# MICROCONTROLLER.net
KiCad netlist of a schematic drawn in Altium Designer
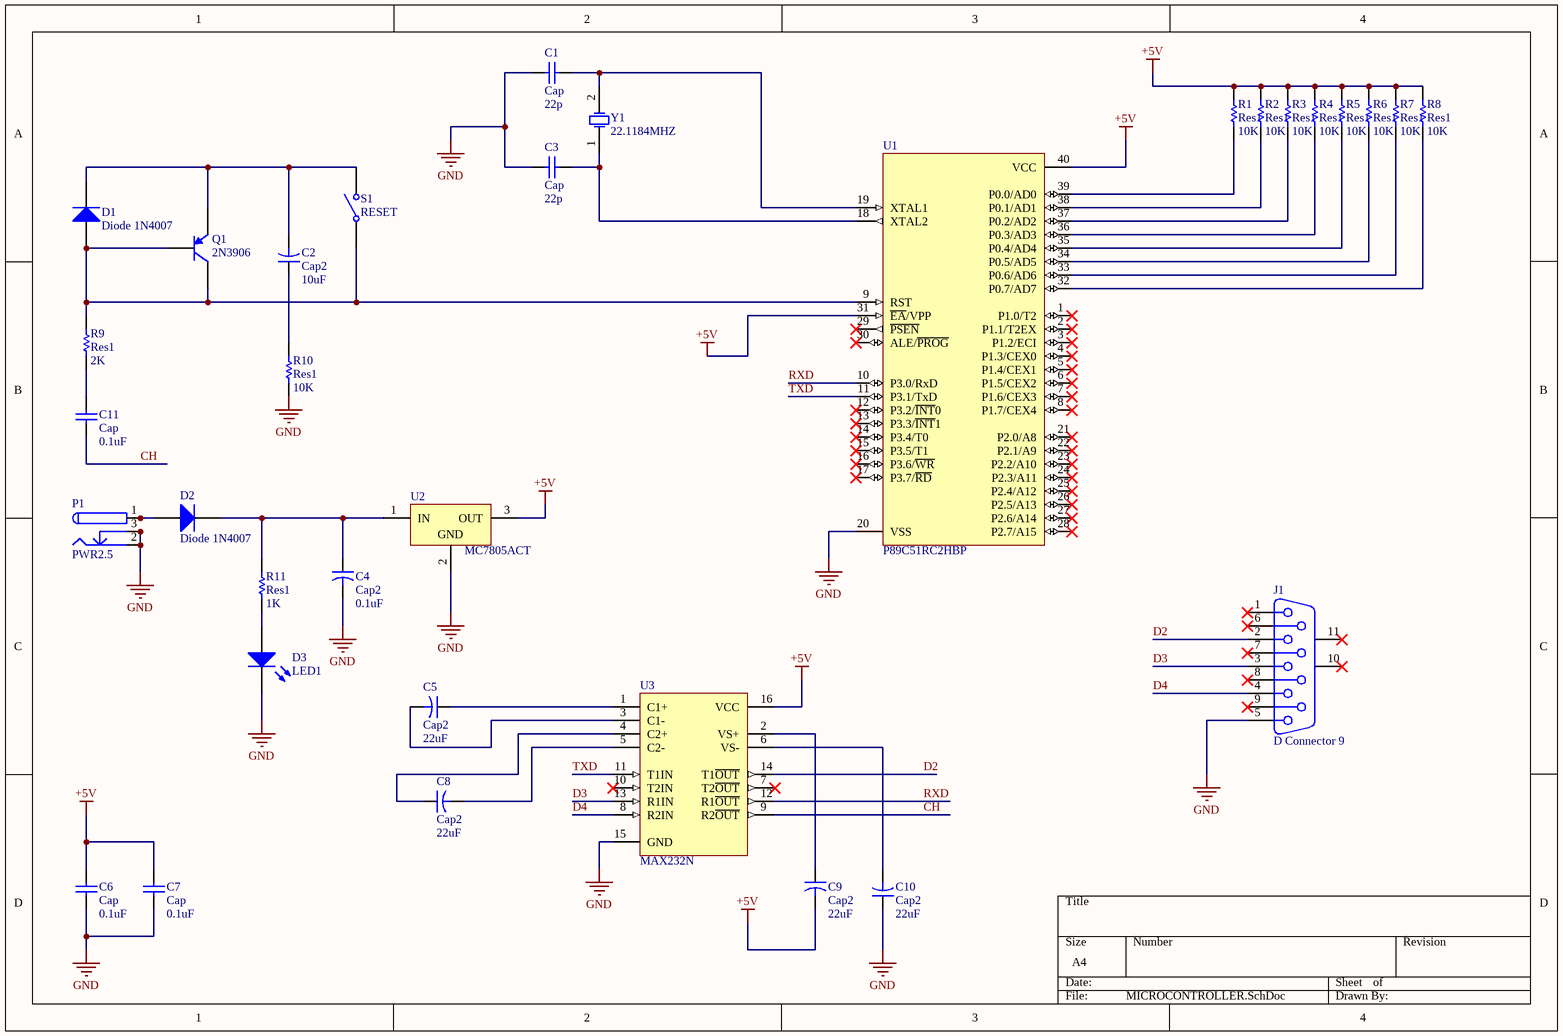
[diagram p0: MICROCONTROLLER.SchDoc]

(export (version "E")
  (design (tool "Eeschema 10.0.6"))
  (components
    (comp (ref "C1")
      (value "Cap")
      (footprint "CAPR2.54-5.1x3.2")
      (description "Capacitor")
      (fields (field (name "ALTIUM_VALUE") "22p") (field (name "PUBLISHER") "Altium Limited"))
      (libsource (lib "Miscellaneous Devices") (part "Cap"))
    )
    (comp (ref "C2")
      (value "Cap2")
      (footprint "CAPR5-4X5")
      (description "Capacitor")
      (fields (field (name "ALTIUM_VALUE") "10uF") (field (name "PUBLISHER") "Altium Limited"))
      (libsource (lib "Miscellaneous Devices") (part "Cap2"))
    )
    (comp (ref "C3")
      (value "Cap")
      (footprint "CAPR2.54-5.1x3.2")
      (description "Capacitor")
      (fields (field (name "ALTIUM_VALUE") "22p") (field (name "PUBLISHER") "Altium Limited"))
      (libsource (lib "Miscellaneous Devices") (part "Cap"))
    )
    (comp (ref "C4")
      (value "Cap2")
      (footprint "CAPR5-4X5")
      (description "Capacitor")
      (fields (field (name "ALTIUM_VALUE") "0.1uF") (field (name "PUBLISHER") "Altium Limited"))
      (libsource (lib "Miscellaneous Devices") (part "Cap2"))
    )
    (comp (ref "C5")
      (value "Cap2")
      (footprint "CAPR5-4X5")
      (description "Capacitor")
      (fields (field (name "ALTIUM_VALUE") "22uF") (field (name "PUBLISHER") "Altium Limited"))
      (libsource (lib "Miscellaneous Devices") (part "Cap2"))
    )
    (comp (ref "C6")
      (value "Cap")
      (footprint "CAPR2.54-5.1x3.2")
      (description "Capacitor")
      (fields (field (name "ALTIUM_VALUE") "0.1uF") (field (name "PUBLISHER") "Altium Limited"))
      (libsource (lib "Miscellaneous Devices") (part "Cap"))
    )
    (comp (ref "C7")
      (value "Cap")
      (footprint "CAPR2.54-5.1x3.2")
      (description "Capacitor")
      (fields (field (name "ALTIUM_VALUE") "0.1uF") (field (name "PUBLISHER") "Altium Limited"))
      (libsource (lib "Miscellaneous Devices") (part "Cap"))
    )
    (comp (ref "C8")
      (value "Cap2")
      (footprint "CAPR5-4X5")
      (description "Capacitor")
      (fields (field (name "ALTIUM_VALUE") "22uF") (field (name "PUBLISHER") "Altium Limited"))
      (libsource (lib "Miscellaneous Devices") (part "Cap2"))
    )
    (comp (ref "C9")
      (value "Cap2")
      (footprint "CAPR5-4X5")
      (description "Capacitor")
      (fields (field (name "ALTIUM_VALUE") "22uF") (field (name "PUBLISHER") "Altium Limited"))
      (libsource (lib "Miscellaneous Devices") (part "Cap2"))
    )
    (comp (ref "C10")
      (value "Cap2")
      (footprint "CAPR5-4X5")
      (description "Capacitor")
      (fields (field (name "ALTIUM_VALUE") "22uF") (field (name "PUBLISHER") "Altium Limited"))
      (libsource (lib "Miscellaneous Devices") (part "Cap2"))
    )
    (comp (ref "C11")
      (value "Cap")
      (footprint "CAPR2.54-5.1x3.2")
      (description "Capacitor")
      (fields (field (name "ALTIUM_VALUE") "0.1uF") (field (name "PUBLISHER") "Altium Limited"))
      (libsource (lib "Miscellaneous Devices") (part "Cap"))
    )
    (comp (ref "D1")
      (value "Diode 1N4007")
      (footprint "DIO10.46-5.3x2.8")
      (description "1 Amp General Purpose Rectifier")
      (fields (field (name "PUBLISHER") "Altium Limited"))
      (libsource (lib "Miscellaneous Devices") (part "Diode 1N4007"))
    )
    (comp (ref "D2")
      (value "Diode 1N4007")
      (footprint "DIO10.46-5.3x2.8")
      (description "1 Amp General Purpose Rectifier")
      (fields (field (name "PUBLISHER") "Altium Limited"))
      (libsource (lib "Miscellaneous Devices") (part "Diode 1N4007"))
    )
    (comp (ref "D3")
      (value "LED1")
      (footprint "LED-1")
      (description "Typical RED GaAs LED")
      (fields (field (name "PUBLISHER") "Altium Limited"))
      (libsource (lib "Miscellaneous Devices") (part "LED1"))
    )
    (comp (ref "J1")
      (value "D Connector 9")
      (footprint "DSUB1.385-2H9")
      (description "Receptacle Assembly, 9 Position, Right Angle")
      (fields (field (name "PUBLISHER") "Altium Limited"))
      (libsource (lib "Miscellaneous Connectors") (part "D Connector 9"))
    )
    (comp (ref "P1")
      (value "PWR2.5")
      (footprint "KLD-0202")
      (description "Low Voltage Power Supply Connector")
      (fields (field (name "PUBLISHER") "Altium Limited"))
      (libsource (lib "Miscellaneous Connectors") (part "PWR2.5"))
    )
    (comp (ref "Q1")
      (value "2N3906")
      (footprint "BCY-W3/E4")
      (description "PNP General Purpose Amplifier")
      (fields (field (name "PUBLISHER") "Altium Limited"))
      (libsource (lib "Miscellaneous Devices") (part "2N3906"))
    )
    (comp (ref "R1")
      (value "Res1")
      (footprint "AXIAL-0.3")
      (description "Resistor")
      (fields (field (name "ALTIUM_VALUE") "10K") (field (name "PUBLISHER") "Altium Limited"))
      (libsource (lib "Miscellaneous Devices") (part "Res1"))
    )
    (comp (ref "R2")
      (value "Res1")
      (footprint "AXIAL-0.3")
      (description "Resistor")
      (fields (field (name "ALTIUM_VALUE") "10K") (field (name "PUBLISHER") "Altium Limited"))
      (libsource (lib "Miscellaneous Devices") (part "Res1"))
    )
    (comp (ref "R3")
      (value "Res1")
      (footprint "AXIAL-0.3")
      (description "Resistor")
      (fields (field (name "ALTIUM_VALUE") "10K") (field (name "PUBLISHER") "Altium Limited"))
      (libsource (lib "Miscellaneous Devices") (part "Res1"))
    )
    (comp (ref "R4")
      (value "Res1")
      (footprint "AXIAL-0.3")
      (description "Resistor")
      (fields (field (name "ALTIUM_VALUE") "10K") (field (name "PUBLISHER") "Altium Limited"))
      (libsource (lib "Miscellaneous Devices") (part "Res1"))
    )
    (comp (ref "R5")
      (value "Res1")
      (footprint "AXIAL-0.3")
      (description "Resistor")
      (fields (field (name "ALTIUM_VALUE") "10K") (field (name "PUBLISHER") "Altium Limited"))
      (libsource (lib "Miscellaneous Devices") (part "Res1"))
    )
    (comp (ref "R6")
      (value "Res1")
      (footprint "AXIAL-0.3")
      (description "Resistor")
      (fields (field (name "ALTIUM_VALUE") "10K") (field (name "PUBLISHER") "Altium Limited"))
      (libsource (lib "Miscellaneous Devices") (part "Res1"))
    )
    (comp (ref "R7")
      (value "Res1")
      (footprint "AXIAL-0.3")
      (description "Resistor")
      (fields (field (name "ALTIUM_VALUE") "10K") (field (name "PUBLISHER") "Altium Limited"))
      (libsource (lib "Miscellaneous Devices") (part "Res1"))
    )
    (comp (ref "R8")
      (value "Res1")
      (footprint "AXIAL-0.3")
      (description "Resistor")
      (fields (field (name "ALTIUM_VALUE") "10K") (field (name "PUBLISHER") "Altium Limited"))
      (libsource (lib "Miscellaneous Devices") (part "Res1"))
    )
    (comp (ref "R9")
      (value "Res1")
      (footprint "AXIAL-0.3")
      (description "Resistor")
      (fields (field (name "ALTIUM_VALUE") "2K") (field (name "PUBLISHER") "Altium Limited"))
      (libsource (lib "Miscellaneous Devices") (part "Res1"))
    )
    (comp (ref "R10")
      (value "Res1")
      (footprint "AXIAL-0.3")
      (description "Resistor")
      (fields (field (name "ALTIUM_VALUE") "10K") (field (name "PUBLISHER") "Altium Limited"))
      (libsource (lib "Miscellaneous Devices") (part "Res1"))
    )
    (comp (ref "R11")
      (value "Res1")
      (footprint "AXIAL-0.3")
      (description "Resistor")
      (fields (field (name "ALTIUM_VALUE") "1K") (field (name "PUBLISHER") "Altium Limited"))
      (libsource (lib "Miscellaneous Devices") (part "Res1"))
    )
    (comp (ref "S1")
      (value "RESET")
      (footprint "SPST-2")
      (description "Single-Pole, Single-Throw Switch")
      (fields (field (name "PUBLISHER") "Altium Limited"))
      (libsource (lib "Miscellaneous Devices") (part "SW-SPST"))
    )
    (comp (ref "U1")
      (value "P89C51RC2HBP")
      (footprint "SOT129-1")
      (description "80C51 8-Bit Flash Microcontroller Family, 32 kB ISP/IAP Flash with 512 B RAM.")
      (fields (field (name "PUBLISHER") "Altium Limited"))
      (libsource (lib "Philips Microcontroller 8-Bit") (part "P89C51RC2HBP"))
    )
    (comp (ref "U2")
      (value "MC7805ACT")
      (footprint "221A-04")
      (description "3-Terminal Positive Fixed Voltage Regulator")
      (fields (field (name "PUBLISHER") "Altium Limited"))
      (libsource (lib "Motorola Power Mgt Voltage Regulator") (part "MC7805ACT"))
    )
    (comp (ref "U3")
      (value "MAX232N")
      (footprint "N016")
      (description "Dual EIA-232 Driver/Receiver")
      (fields (field (name "PUBLISHER") "Altium Limited"))
      (libsource (lib "TI Interface Line Transceiver") (part "MAX232N"))
    )
    (comp (ref "Y1")
      (value "22.1184MHZ")
      (footprint "HC-49U")
      (description "Crystal Oscillator")
      (fields (field (name "PUBLISHER") "Altium Limited"))
      (libsource (lib "ECS Crystal Oscillator") (part "ECS-18-13-1"))
    )
  )
  (nets
    (net (code "1") (name "+5V") (class "Default")
      (node (ref "C6") (pin "2") (pinfunction "2_2") (pintype "passive"))
      (node (ref "C7") (pin "1") (pinfunction "1_1") (pintype "passive"))
      (node (ref "C9") (pin "2") (pinfunction "2_2") (pintype "passive"))
      (node (ref "R1") (pin "2") (pinfunction "2_2") (pintype "passive"))
      (node (ref "R2") (pin "2") (pinfunction "2_2") (pintype "passive"))
      (node (ref "R3") (pin "2") (pinfunction "2_2") (pintype "passive"))
      (node (ref "R4") (pin "2") (pinfunction "2_2") (pintype "passive"))
      (node (ref "R5") (pin "2") (pinfunction "2_2") (pintype "passive"))
      (node (ref "R6") (pin "2") (pinfunction "2_2") (pintype "passive"))
      (node (ref "R7") (pin "2") (pinfunction "2_2") (pintype "passive"))
      (node (ref "R8") (pin "2") (pinfunction "2_2") (pintype "passive"))
      (node (ref "U1") (pin "31") (pinfunction "~{EA}/VPP_31") (pintype "input"))
      (node (ref "U1") (pin "40") (pinfunction "VCC_40") (pintype "power_in"))
      (node (ref "U2") (pin "3") (pinfunction "OUT_3") (pintype "power_in"))
      (node (ref "U3") (pin "16") (pinfunction "VCC_16") (pintype "power_in"))
    )
    (net (code "2") (name "/CH") (class "Default")
      (node (ref "C11") (pin "1") (pinfunction "1_1") (pintype "passive"))
      (node (ref "U3") (pin "9") (pinfunction "R2~{OUT}_9") (pintype "output"))
    )
    (net (code "3") (name "/D2") (class "Default")
      (node (ref "J1") (pin "2") (pinfunction "2_2") (pintype "passive"))
      (node (ref "U3") (pin "14") (pinfunction "T1~{OUT}_14") (pintype "output"))
    )
    (net (code "4") (name "/D3") (class "Default")
      (node (ref "J1") (pin "3") (pinfunction "3_3") (pintype "passive"))
      (node (ref "U3") (pin "13") (pinfunction "R1IN_13") (pintype "input"))
    )
    (net (code "5") (name "/D4") (class "Default")
      (node (ref "J1") (pin "4") (pinfunction "4_4") (pintype "passive"))
      (node (ref "U3") (pin "8") (pinfunction "R2IN_8") (pintype "input"))
    )
    (net (code "6") (name "/RXD") (class "Default")
      (node (ref "U1") (pin "10") (pinfunction "P3.0/RxD_10") (pintype "bidirectional"))
      (node (ref "U3") (pin "12") (pinfunction "R1~{OUT}_12") (pintype "output"))
    )
    (net (code "7") (name "/TXD") (class "Default")
      (node (ref "U1") (pin "11") (pinfunction "P3.1/TxD_11") (pintype "bidirectional"))
      (node (ref "U3") (pin "11") (pinfunction "T1IN_11") (pintype "input"))
    )
    (net (code "8") (name "GND") (class "Default")
      (node (ref "C1") (pin "2") (pinfunction "2_2") (pintype "passive"))
      (node (ref "C10") (pin "1") (pinfunction "1_1") (pintype "passive"))
      (node (ref "C3") (pin "2") (pinfunction "2_2") (pintype "passive"))
      (node (ref "C4") (pin "2") (pinfunction "2_2") (pintype "passive"))
      (node (ref "C6") (pin "1") (pinfunction "1_1") (pintype "passive"))
      (node (ref "C7") (pin "2") (pinfunction "2_2") (pintype "passive"))
      (node (ref "D3") (pin "2") (pinfunction "K_2") (pintype "passive"))
      (node (ref "J1") (pin "5") (pinfunction "5_5") (pintype "passive"))
      (node (ref "P1") (pin "2") (pinfunction "2_2") (pintype "power_in"))
      (node (ref "P1") (pin "2A") (pinfunction "2A_2A") (pintype "power_in"))
      (node (ref "P1") (pin "2B") (pinfunction "2B_2B") (pintype "power_in"))
      (node (ref "P1") (pin "3") (pinfunction "3_3") (pintype "power_in"))
      (node (ref "P1") (pin "3A") (pinfunction "3A_3A") (pintype "power_in"))
      (node (ref "P1") (pin "3B") (pinfunction "3B_3B") (pintype "power_in"))
      (node (ref "R10") (pin "1") (pinfunction "1_1") (pintype "passive"))
      (node (ref "U1") (pin "20") (pinfunction "VSS_20") (pintype "power_in"))
      (node (ref "U2") (pin "2") (pinfunction "GND_2") (pintype "power_in"))
      (node (ref "U3") (pin "15") (pinfunction "GND_15") (pintype "power_in"))
    )
    (net (code "9") (name "Net-(C2-Pad1)") (class "Default")
      (node (ref "C2") (pin "1") (pinfunction "1_1") (pintype "passive"))
      (node (ref "R10") (pin "2") (pinfunction "2_2") (pintype "passive"))
    )
    (net (code "10") (name "Net-(C11-Pad2)") (class "Default")
      (node (ref "C11") (pin "2") (pinfunction "2_2") (pintype "passive"))
      (node (ref "R9") (pin "1") (pinfunction "1_1") (pintype "passive"))
    )
    (net (code "11") (name "Net-(D1-A)") (class "Default")
      (node (ref "D1") (pin "1") (pinfunction "A_1") (pintype "passive"))
      (node (ref "Q1") (pin "2") (pinfunction "B_2") (pintype "passive"))
      (node (ref "Q1") (pin "3") (pinfunction "C_3") (pintype "passive"))
      (node (ref "R9") (pin "2") (pinfunction "2_2") (pintype "passive"))
      (node (ref "S1") (pin "1") (pinfunction "COMMON_1") (pintype "passive"))
      (node (ref "U1") (pin "9") (pinfunction "RST_9") (pintype "input"))
    )
    (net (code "12") (name "Net-(D1-K)") (class "Default")
      (node (ref "C2") (pin "2") (pinfunction "2_2") (pintype "passive"))
      (node (ref "D1") (pin "2") (pinfunction "K_2") (pintype "passive"))
      (node (ref "Q1") (pin "1") (pinfunction "E_1") (pintype "passive"))
      (node (ref "S1") (pin "2") (pinfunction "NO_2") (pintype "passive"))
    )
    (net (code "13") (name "Net-(D2-A)") (class "Default")
      (node (ref "D2") (pin "1") (pinfunction "A_1") (pintype "passive"))
      (node (ref "P1") (pin "1") (pinfunction "1_1") (pintype "power_in"))
      (node (ref "P1") (pin "1A") (pinfunction "1A_1A") (pintype "power_in"))
      (node (ref "P1") (pin "1B") (pinfunction "1B_1B") (pintype "power_in"))
    )
    (net (code "14") (name "Net-(D2-K)") (class "Default")
      (node (ref "C4") (pin "1") (pinfunction "1_1") (pintype "passive"))
      (node (ref "D2") (pin "2") (pinfunction "K_2") (pintype "passive"))
      (node (ref "R11") (pin "2") (pinfunction "2_2") (pintype "passive"))
      (node (ref "U2") (pin "1") (pinfunction "IN_1") (pintype "power_in"))
    )
    (net (code "15") (name "Net-(D3-A)") (class "Default")
      (node (ref "D3") (pin "1") (pinfunction "A_1") (pintype "passive"))
      (node (ref "R11") (pin "1") (pinfunction "1_1") (pintype "passive"))
    )
    (net (code "16") (name "Net-(U1-P0.0{slash}AD0)") (class "Default")
      (node (ref "R1") (pin "1") (pinfunction "1_1") (pintype "passive"))
      (node (ref "U1") (pin "39") (pinfunction "P0.0/AD0_39") (pintype "bidirectional"))
    )
    (net (code "17") (name "Net-(U1-P0.1{slash}AD1)") (class "Default")
      (node (ref "R2") (pin "1") (pinfunction "1_1") (pintype "passive"))
      (node (ref "U1") (pin "38") (pinfunction "P0.1/AD1_38") (pintype "bidirectional"))
    )
    (net (code "18") (name "Net-(U1-P0.2{slash}AD2)") (class "Default")
      (node (ref "R3") (pin "1") (pinfunction "1_1") (pintype "passive"))
      (node (ref "U1") (pin "37") (pinfunction "P0.2/AD2_37") (pintype "bidirectional"))
    )
    (net (code "19") (name "Net-(U1-P0.3{slash}AD3)") (class "Default")
      (node (ref "R4") (pin "1") (pinfunction "1_1") (pintype "passive"))
      (node (ref "U1") (pin "36") (pinfunction "P0.3/AD3_36") (pintype "bidirectional"))
    )
    (net (code "20") (name "Net-(U1-P0.4{slash}AD4)") (class "Default")
      (node (ref "R5") (pin "1") (pinfunction "1_1") (pintype "passive"))
      (node (ref "U1") (pin "35") (pinfunction "P0.4/AD4_35") (pintype "bidirectional"))
    )
    (net (code "21") (name "Net-(U1-P0.5{slash}AD5)") (class "Default")
      (node (ref "R6") (pin "1") (pinfunction "1_1") (pintype "passive"))
      (node (ref "U1") (pin "34") (pinfunction "P0.5/AD5_34") (pintype "bidirectional"))
    )
    (net (code "22") (name "Net-(U1-P0.6{slash}AD6)") (class "Default")
      (node (ref "R7") (pin "1") (pinfunction "1_1") (pintype "passive"))
      (node (ref "U1") (pin "33") (pinfunction "P0.6/AD6_33") (pintype "bidirectional"))
    )
    (net (code "23") (name "Net-(U1-P0.7{slash}AD7)") (class "Default")
      (node (ref "R8") (pin "1") (pinfunction "1_1") (pintype "passive"))
      (node (ref "U1") (pin "32") (pinfunction "P0.7/AD7_32") (pintype "bidirectional"))
    )
    (net (code "24") (name "Net-(U1-XTAL1)") (class "Default")
      (node (ref "C1") (pin "1") (pinfunction "1_1") (pintype "passive"))
      (node (ref "U1") (pin "19") (pinfunction "XTAL1_19") (pintype "input"))
      (node (ref "Y1") (pin "2") (pinfunction "OSC2_2") (pintype "passive"))
    )
    (net (code "25") (name "Net-(U1-XTAL2)") (class "Default")
      (node (ref "C3") (pin "1") (pinfunction "1_1") (pintype "passive"))
      (node (ref "U1") (pin "18") (pinfunction "XTAL2_18") (pintype "output"))
      (node (ref "Y1") (pin "1") (pinfunction "OSC1_1") (pintype "passive"))
    )
    (net (code "26") (name "Net-(U3-C1+)") (class "Default")
      (node (ref "C5") (pin "1") (pinfunction "1_1") (pintype "passive"))
      (node (ref "U3") (pin "1") (pinfunction "C1+_1") (pintype "passive"))
    )
    (net (code "27") (name "Net-(U3-C1-)") (class "Default")
      (node (ref "C5") (pin "2") (pinfunction "2_2") (pintype "passive"))
      (node (ref "U3") (pin "3") (pinfunction "C1-_3") (pintype "passive"))
    )
    (net (code "28") (name "Net-(U3-C2+)") (class "Default")
      (node (ref "C8") (pin "1") (pinfunction "1_1") (pintype "passive"))
      (node (ref "U3") (pin "4") (pinfunction "C2+_4") (pintype "passive"))
    )
    (net (code "29") (name "Net-(U3-C2-)") (class "Default")
      (node (ref "C8") (pin "2") (pinfunction "2_2") (pintype "passive"))
      (node (ref "U3") (pin "5") (pinfunction "C2-_5") (pintype "passive"))
    )
    (net (code "30") (name "Net-(U3-VS+)") (class "Default")
      (node (ref "C9") (pin "1") (pinfunction "1_1") (pintype "passive"))
      (node (ref "U3") (pin "2") (pinfunction "VS+_2") (pintype "power_in"))
    )
    (net (code "31") (name "Net-(U3-VS-)") (class "Default")
      (node (ref "C10") (pin "2") (pinfunction "2_2") (pintype "passive"))
      (node (ref "U3") (pin "6") (pinfunction "VS-_6") (pintype "power_in"))
    )
    (net (code "32") (name "unconnected-(J1-MH1-Pad10)") (class "Default")
      (node (ref "J1") (pin "10") (pinfunction "MH1_10") (pintype "passive+no_connect"))
    )
    (net (code "33") (name "unconnected-(J1-MH2-Pad11)") (class "Default")
      (node (ref "J1") (pin "11") (pinfunction "MH2_11") (pintype "passive+no_connect"))
    )
    (net (code "34") (name "unconnected-(J1-Pad1)") (class "Default")
      (node (ref "J1") (pin "1") (pinfunction "1_1") (pintype "passive+no_connect"))
    )
    (net (code "35") (name "unconnected-(J1-Pad6)") (class "Default")
      (node (ref "J1") (pin "6") (pinfunction "6_6") (pintype "passive+no_connect"))
    )
    (net (code "36") (name "unconnected-(J1-Pad7)") (class "Default")
      (node (ref "J1") (pin "7") (pinfunction "7_7") (pintype "passive+no_connect"))
    )
    (net (code "37") (name "unconnected-(J1-Pad8)") (class "Default")
      (node (ref "J1") (pin "8") (pinfunction "8_8") (pintype "passive+no_connect"))
    )
    (net (code "38") (name "unconnected-(J1-Pad9)") (class "Default")
      (node (ref "J1") (pin "9") (pinfunction "9_9") (pintype "passive+no_connect"))
    )
    (net (code "39") (name "unconnected-(U1-ALE{slash}~{PROG}-Pad30)") (class "Default")
      (node (ref "U1") (pin "30") (pinfunction "ALE/~{PROG}_30") (pintype "bidirectional+no_connect"))
    )
    (net (code "40") (name "unconnected-(U1-P1.0{slash}T2-Pad1)") (class "Default")
      (node (ref "U1") (pin "1") (pinfunction "P1.0/T2_1") (pintype "bidirectional+no_connect"))
    )
    (net (code "41") (name "unconnected-(U1-P1.1{slash}T2EX-Pad2)") (class "Default")
      (node (ref "U1") (pin "2") (pinfunction "P1.1/T2EX_2") (pintype "bidirectional+no_connect"))
    )
    (net (code "42") (name "unconnected-(U1-P1.2{slash}ECI-Pad3)") (class "Default")
      (node (ref "U1") (pin "3") (pinfunction "P1.2/ECI_3") (pintype "bidirectional+no_connect"))
    )
    (net (code "43") (name "unconnected-(U1-P1.3{slash}CEX0-Pad4)") (class "Default")
      (node (ref "U1") (pin "4") (pinfunction "P1.3/CEX0_4") (pintype "bidirectional+no_connect"))
    )
    (net (code "44") (name "unconnected-(U1-P1.4{slash}CEX1-Pad5)") (class "Default")
      (node (ref "U1") (pin "5") (pinfunction "P1.4/CEX1_5") (pintype "bidirectional+no_connect"))
    )
    (net (code "45") (name "unconnected-(U1-P1.5{slash}CEX2-Pad6)") (class "Default")
      (node (ref "U1") (pin "6") (pinfunction "P1.5/CEX2_6") (pintype "bidirectional+no_connect"))
    )
    (net (code "46") (name "unconnected-(U1-P1.6{slash}CEX3-Pad7)") (class "Default")
      (node (ref "U1") (pin "7") (pinfunction "P1.6/CEX3_7") (pintype "bidirectional+no_connect"))
    )
    (net (code "47") (name "unconnected-(U1-P1.7{slash}CEX4-Pad8)") (class "Default")
      (node (ref "U1") (pin "8") (pinfunction "P1.7/CEX4_8") (pintype "bidirectional+no_connect"))
    )
    (net (code "48") (name "unconnected-(U1-P2.0{slash}A8-Pad21)") (class "Default")
      (node (ref "U1") (pin "21") (pinfunction "P2.0/A8_21") (pintype "bidirectional+no_connect"))
    )
    (net (code "49") (name "unconnected-(U1-P2.1{slash}A9-Pad22)") (class "Default")
      (node (ref "U1") (pin "22") (pinfunction "P2.1/A9_22") (pintype "bidirectional+no_connect"))
    )
    (net (code "50") (name "unconnected-(U1-P2.2{slash}A10-Pad23)") (class "Default")
      (node (ref "U1") (pin "23") (pinfunction "P2.2/A10_23") (pintype "bidirectional+no_connect"))
    )
    (net (code "51") (name "unconnected-(U1-P2.3{slash}A11-Pad24)") (class "Default")
      (node (ref "U1") (pin "24") (pinfunction "P2.3/A11_24") (pintype "bidirectional+no_connect"))
    )
    (net (code "52") (name "unconnected-(U1-P2.4{slash}A12-Pad25)") (class "Default")
      (node (ref "U1") (pin "25") (pinfunction "P2.4/A12_25") (pintype "bidirectional+no_connect"))
    )
    (net (code "53") (name "unconnected-(U1-P2.5{slash}A13-Pad26)") (class "Default")
      (node (ref "U1") (pin "26") (pinfunction "P2.5/A13_26") (pintype "bidirectional+no_connect"))
    )
    (net (code "54") (name "unconnected-(U1-P2.6{slash}A14-Pad27)") (class "Default")
      (node (ref "U1") (pin "27") (pinfunction "P2.6/A14_27") (pintype "bidirectional+no_connect"))
    )
    (net (code "55") (name "unconnected-(U1-P2.7{slash}A15-Pad28)") (class "Default")
      (node (ref "U1") (pin "28") (pinfunction "P2.7/A15_28") (pintype "bidirectional+no_connect"))
    )
    (net (code "56") (name "unconnected-(U1-P3.2{slash}~{INT}0-Pad12)") (class "Default")
      (node (ref "U1") (pin "12") (pinfunction "P3.2/~{INT}0_12") (pintype "bidirectional+no_connect"))
    )
    (net (code "57") (name "unconnected-(U1-P3.3{slash}~{INT}1-Pad13)") (class "Default")
      (node (ref "U1") (pin "13") (pinfunction "P3.3/~{INT}1_13") (pintype "bidirectional+no_connect"))
    )
    (net (code "58") (name "unconnected-(U1-P3.4{slash}T0-Pad14)") (class "Default")
      (node (ref "U1") (pin "14") (pinfunction "P3.4/T0_14") (pintype "bidirectional+no_connect"))
    )
    (net (code "59") (name "unconnected-(U1-P3.5{slash}T1-Pad15)") (class "Default")
      (node (ref "U1") (pin "15") (pinfunction "P3.5/T1_15") (pintype "bidirectional+no_connect"))
    )
    (net (code "60") (name "unconnected-(U1-P3.6{slash}~{WR}-Pad16)") (class "Default")
      (node (ref "U1") (pin "16") (pinfunction "P3.6/~{WR}_16") (pintype "bidirectional+no_connect"))
    )
    (net (code "61") (name "unconnected-(U1-P3.7{slash}~{RD}-Pad17)") (class "Default")
      (node (ref "U1") (pin "17") (pinfunction "P3.7/~{RD}_17") (pintype "bidirectional+no_connect"))
    )
    (net (code "62") (name "unconnected-(U1-~{PSEN}-Pad29)") (class "Default")
      (node (ref "U1") (pin "29") (pinfunction "~{PSEN}_29") (pintype "output+no_connect"))
    )
    (net (code "63") (name "unconnected-(U3-T2IN-Pad10)") (class "Default")
      (node (ref "U3") (pin "10") (pinfunction "T2IN_10") (pintype "input+no_connect"))
    )
    (net (code "64") (name "unconnected-(U3-T2~{OUT}-Pad7)") (class "Default")
      (node (ref "U3") (pin "7") (pinfunction "T2~{OUT}_7") (pintype "output+no_connect"))
    )
  )
)
